# rs232_part.net
KiCad netlist of a schematic drawn in Altium Designer
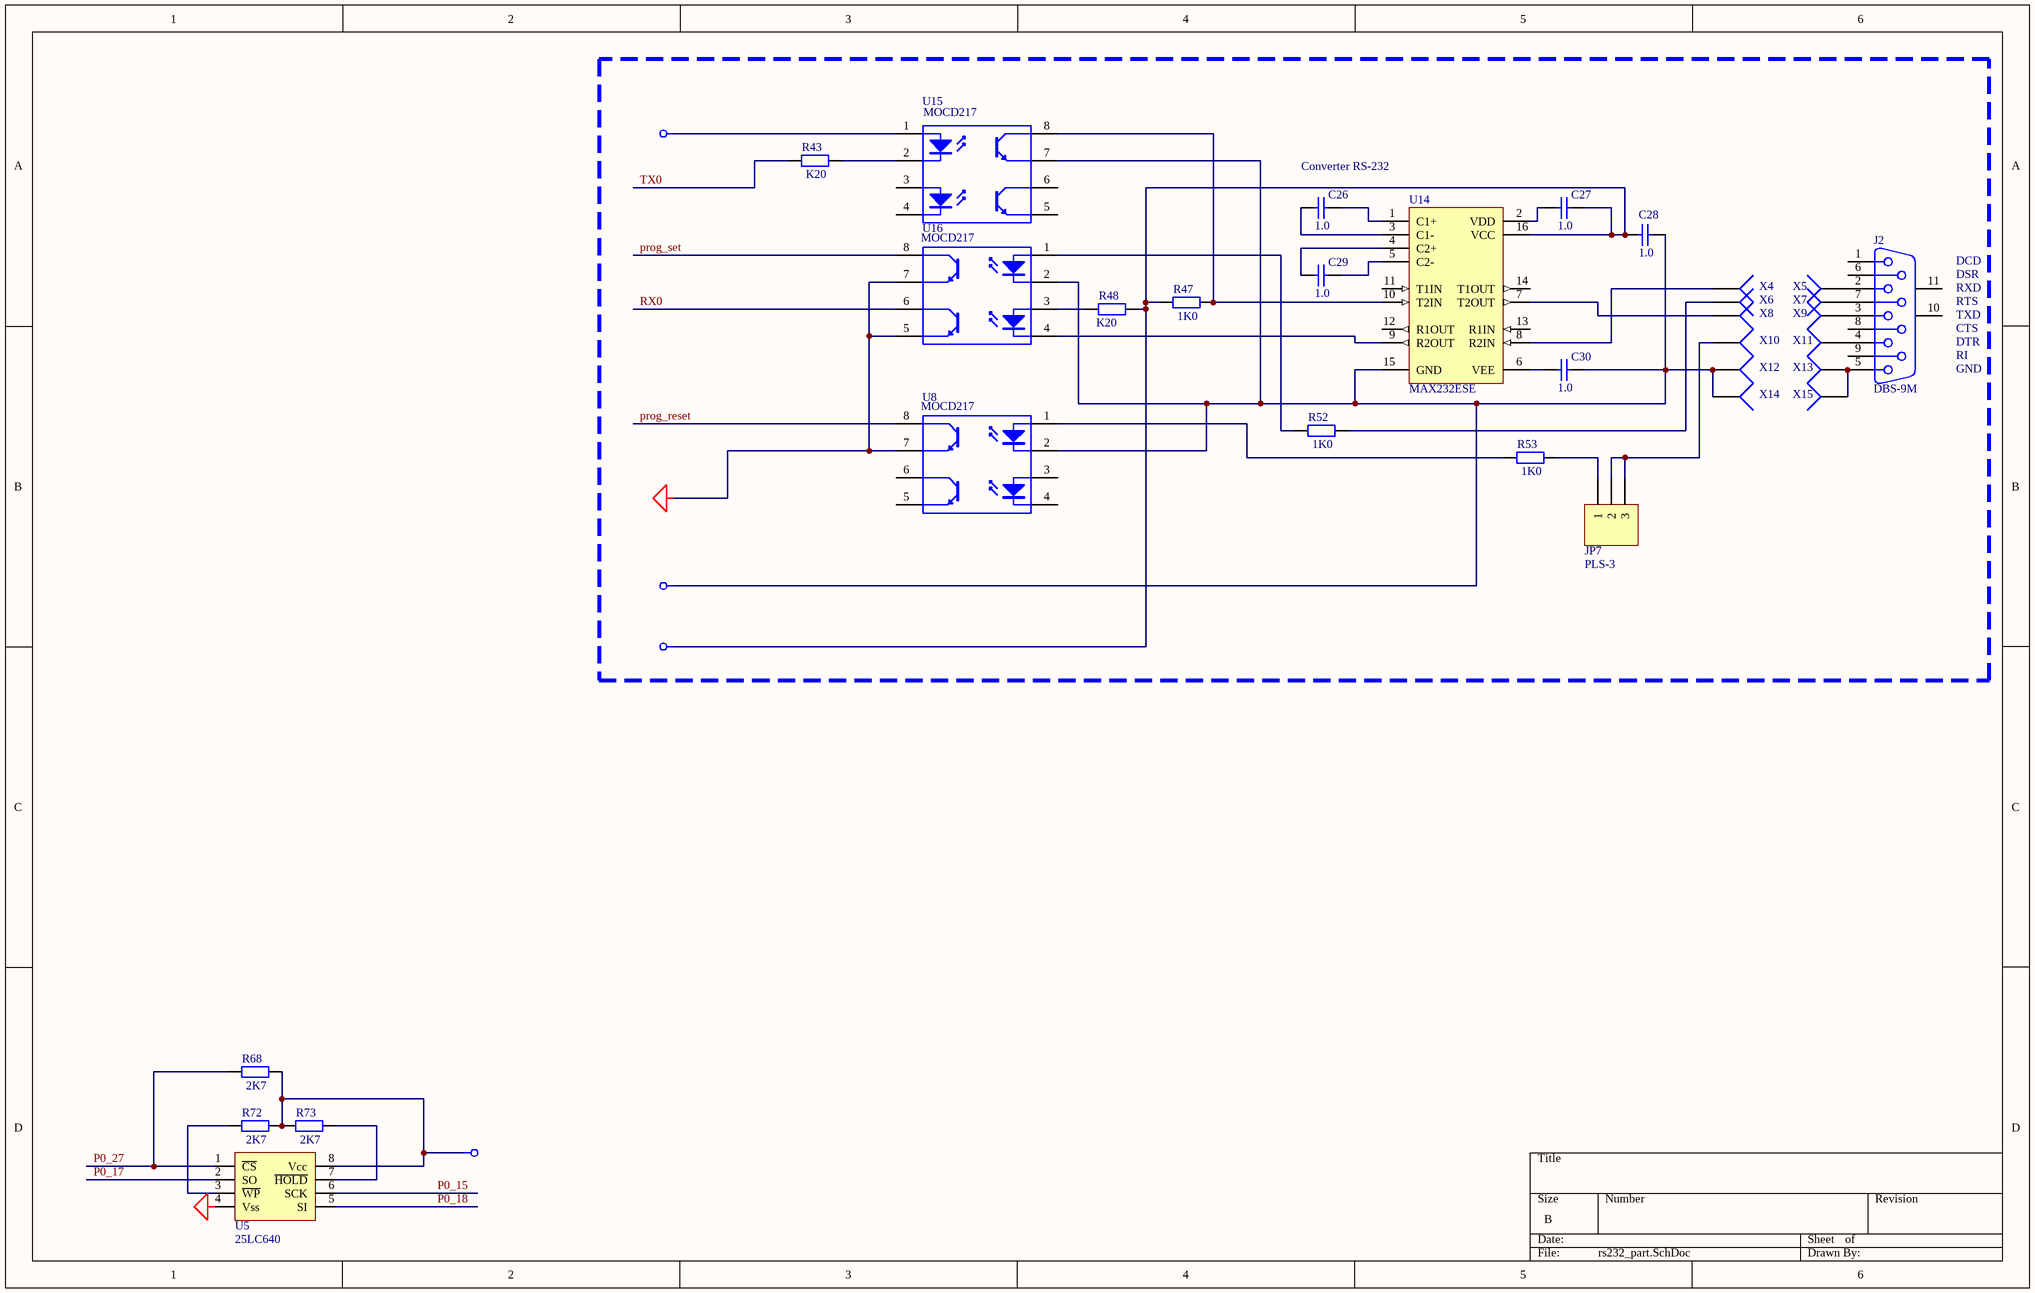
[diagram p0: rs232_part.SchDoc]

(export (version "E")
  (design (tool "Eeschema 10.0.6"))
  (components
    (comp (ref "C26")
      (value "1.0")
      (footprint "C3216-1206")
      (description "Capacitor (Semiconductor SIM Model)")
      (fields (field (name "MANUFACTURER") "Generic Components") (field (name "PUBLISHER") "Altium Limited"))
      (libsource (lib "Miscellaneous Devices") (part "Cap Semi"))
    )
    (comp (ref "C27")
      (value "1.0")
      (footprint "_1206")
      (description "Capacitor (Semiconductor SIM Model)")
      (fields (field (name "MANUFACTURER") "Generic Components") (field (name "PUBLISHER") "Altium Limited"))
      (libsource (lib "Miscellaneous Devices") (part "Cap Semi"))
    )
    (comp (ref "C28")
      (value "1.0")
      (footprint "C3216-1206")
      (description "Capacitor (Semiconductor SIM Model)")
      (fields (field (name "MANUFACTURER") "Generic Components") (field (name "PUBLISHER") "Altium Limited"))
      (libsource (lib "Miscellaneous Devices") (part "Cap Semi"))
    )
    (comp (ref "C29")
      (value "1.0")
      (footprint "C3216-1206")
      (description "Capacitor (Semiconductor SIM Model)")
      (fields (field (name "MANUFACTURER") "Generic Components") (field (name "PUBLISHER") "Altium Limited"))
      (libsource (lib "Miscellaneous Devices") (part "Cap Semi"))
    )
    (comp (ref "C30")
      (value "1.0")
      (footprint "C3216-1206")
      (description "Capacitor (Semiconductor SIM Model)")
      (fields (field (name "MANUFACTURER") "Generic Components") (field (name "PUBLISHER") "Altium Limited"))
      (libsource (lib "Miscellaneous Devices") (part "Cap Semi"))
    )
    (comp (ref "J2")
      (value "DBS-9M")
      (footprint "DSUB_N9")
      (description "Receptacle Assembly, 9 Position, Right Angle")
      (fields (field (name "MANUFACTURER") "Generic Components") (field (name "PUBLISHER") "Altium Limited"))
      (libsource (lib "Miscellaneous Connectors") (part "D Connector 9"))
    )
    (comp (ref "JP7")
      (value "PLS-3")
      (footprint "HDR1X3")
      (description "Header, 3-Pin")
      (fields (field (name "MANUFACTURER") "Generic Components") (field (name "PUBLISHER") "Altium Limited"))
      (libsource (lib "Miscellaneous Connectors") (part "Header 3"))
    )
    (comp (ref "R43")
      (value "K20")
      (footprint "_1206")
      (description "Resistor")
      (fields (field (name "MANUFACTURER") "Generic Components") (field (name "PUBLISHER") "Altium Limited"))
      (libsource (lib "Miscellaneous Devices") (part "Res2"))
    )
    (comp (ref "R47")
      (value "1K0")
      (footprint "_1206")
      (description "Resistor")
      (fields (field (name "MANUFACTURER") "Generic Components") (field (name "PUBLISHER") "Altium Limited"))
      (libsource (lib "Miscellaneous Devices") (part "Res2"))
    )
    (comp (ref "R48")
      (value "K20")
      (footprint "_1206")
      (description "Resistor")
      (fields (field (name "MANUFACTURER") "Generic Components") (field (name "PUBLISHER") "Altium Limited"))
      (libsource (lib "Miscellaneous Devices") (part "Res2"))
    )
    (comp (ref "R52")
      (value "1K0")
      (footprint "_1206")
      (description "Resistor")
      (fields (field (name "MANUFACTURER") "Generic Components") (field (name "PUBLISHER") "Altium Limited"))
      (libsource (lib "Miscellaneous Devices") (part "Res2"))
    )
    (comp (ref "R53")
      (value "1K0")
      (footprint "_1206")
      (description "Resistor")
      (fields (field (name "MANUFACTURER") "Generic Components") (field (name "PUBLISHER") "Altium Limited"))
      (libsource (lib "Miscellaneous Devices") (part "Res2"))
    )
    (comp (ref "R68")
      (value "2K7")
      (footprint "_1206")
      (description "Resistor")
      (fields (field (name "MANUFACTURER") "Generic Components") (field (name "PUBLISHER") "Altium Limited"))
      (libsource (lib "Miscellaneous Devices") (part "Res2"))
    )
    (comp (ref "R72")
      (value "2K7")
      (footprint "_1206")
      (description "Resistor")
      (fields (field (name "MANUFACTURER") "Generic Components") (field (name "PUBLISHER") "Altium Limited"))
      (libsource (lib "Miscellaneous Devices") (part "Res2"))
    )
    (comp (ref "R73")
      (value "2K7")
      (footprint "_1206")
      (description "Resistor")
      (fields (field (name "MANUFACTURER") "Generic Components") (field (name "PUBLISHER") "Altium Limited"))
      (libsource (lib "Miscellaneous Devices") (part "Res2"))
    )
    (comp (ref "U5") (value "25LC640") (footprint "SO-G8/D5") (libsource (lib "PAL") (part "25LC640")))
    (comp (ref "U8") (value "MOCD217") (footprint "SO-G8") (libsource (lib "PAL") (part "MOCD217")))
    (comp (ref "U14")
      (value "MAX232ESE")
      (footprint "SO-G16")
      (description "+5V Powered, Multi-Channel RS-232 Driver/Receiver")
      (fields (field (name "MANUFACTURER") "Maxim") (field (name "PUBLISHER") "Altium Limited"))
      (libsource (lib "Maxim Communication Transceiver") (part "MAX232ESE"))
    )
    (comp (ref "U15") (value "MOCD217") (footprint "SO-G8") (libsource (lib "PAL") (part "MOCD217")))
    (comp (ref "U16") (value "MOCD217") (footprint "SO-G8") (libsource (lib "PAL") (part "MOCD217")))
    (comp (ref "X4")
      (value "~")
      (footprint "PIN1")
      (description "Socket")
      (fields (field (name "MANUFACTURER") "Generic Components") (field (name "PUBLISHER") "Altium Limited"))
      (libsource (lib "Miscellaneous Connectors") (part "Socket"))
    )
    (comp (ref "X5")
      (value "~")
      (footprint "PIN1")
      (description "Socket")
      (fields (field (name "MANUFACTURER") "Generic Components") (field (name "PUBLISHER") "Altium Limited"))
      (libsource (lib "Miscellaneous Connectors") (part "Socket"))
    )
    (comp (ref "X6")
      (value "~")
      (footprint "PIN1")
      (description "Socket")
      (fields (field (name "MANUFACTURER") "Generic Components") (field (name "PUBLISHER") "Altium Limited"))
      (libsource (lib "Miscellaneous Connectors") (part "Socket"))
    )
    (comp (ref "X7")
      (value "~")
      (footprint "PIN1")
      (description "Socket")
      (fields (field (name "MANUFACTURER") "Generic Components") (field (name "PUBLISHER") "Altium Limited"))
      (libsource (lib "Miscellaneous Connectors") (part "Socket"))
    )
    (comp (ref "X8")
      (value "~")
      (footprint "PIN1")
      (description "Socket")
      (fields (field (name "MANUFACTURER") "Generic Components") (field (name "PUBLISHER") "Altium Limited"))
      (libsource (lib "Miscellaneous Connectors") (part "Socket"))
    )
    (comp (ref "X9")
      (value "~")
      (footprint "PIN1")
      (description "Socket")
      (fields (field (name "MANUFACTURER") "Generic Components") (field (name "PUBLISHER") "Altium Limited"))
      (libsource (lib "Miscellaneous Connectors") (part "Socket"))
    )
    (comp (ref "X10")
      (value "~")
      (footprint "PIN1")
      (description "Socket")
      (fields (field (name "MANUFACTURER") "Generic Components") (field (name "PUBLISHER") "Altium Limited"))
      (libsource (lib "Miscellaneous Connectors") (part "Socket"))
    )
    (comp (ref "X11")
      (value "~")
      (footprint "PIN1")
      (description "Socket")
      (fields (field (name "MANUFACTURER") "Generic Components") (field (name "PUBLISHER") "Altium Limited"))
      (libsource (lib "Miscellaneous Connectors") (part "Socket"))
    )
    (comp (ref "X12")
      (value "~")
      (footprint "PIN1")
      (description "Socket")
      (fields (field (name "MANUFACTURER") "Generic Components") (field (name "PUBLISHER") "Altium Limited"))
      (libsource (lib "Miscellaneous Connectors") (part "Socket"))
    )
    (comp (ref "X13")
      (value "~")
      (footprint "PIN1")
      (description "Socket")
      (fields (field (name "MANUFACTURER") "Generic Components") (field (name "PUBLISHER") "Altium Limited"))
      (libsource (lib "Miscellaneous Connectors") (part "Socket"))
    )
    (comp (ref "X14")
      (value "~")
      (footprint "PIN1")
      (description "Socket")
      (fields (field (name "MANUFACTURER") "Generic Components") (field (name "PUBLISHER") "Altium Limited"))
      (libsource (lib "Miscellaneous Connectors") (part "Socket"))
    )
    (comp (ref "X15")
      (value "~")
      (footprint "PIN1")
      (description "Socket")
      (fields (field (name "MANUFACTURER") "Generic Components") (field (name "PUBLISHER") "Altium Limited"))
      (libsource (lib "Miscellaneous Connectors") (part "Socket"))
    )
  )
  (nets
    (net (code "1") (name "+3v3") (class "Default")
      (node (ref "U15") (pin "1") (pinfunction "A_1") (pintype "passive"))
    )
    (net (code "2") (name "+5v") (class "Default")
      (node (ref "R68") (pin "2") (pinfunction "2_2") (pintype "passive"))
      (node (ref "R72") (pin "2") (pinfunction "2_2") (pintype "passive"))
      (node (ref "R73") (pin "1") (pinfunction "1_1") (pintype "passive"))
      (node (ref "U5") (pin "8") (pinfunction "Vcc_8") (pintype "passive"))
    )
    (net (code "3") (name "+5v_iz") (class "Default")
      (node (ref "C27") (pin "2") (pinfunction "2_2") (pintype "passive"))
      (node (ref "C28") (pin "1") (pinfunction "1_1") (pintype "passive"))
      (node (ref "R47") (pin "1") (pinfunction "1_1") (pintype "passive"))
      (node (ref "R48") (pin "2") (pinfunction "2_2") (pintype "passive"))
      (node (ref "U14") (pin "16") (pinfunction "VCC_16") (pintype "power_in"))
    )
    (net (code "4") (name "-5v_iz") (class "Default")
      (node (ref "C28") (pin "2") (pinfunction "2_2") (pintype "passive"))
      (node (ref "C30") (pin "2") (pinfunction "2_2") (pintype "passive"))
      (node (ref "U14") (pin "15") (pinfunction "GND_15") (pintype "power_in"))
      (node (ref "U15") (pin "7") (pinfunction "E_7") (pintype "passive"))
      (node (ref "U16") (pin "2") (pinfunction "K_2") (pintype "passive"))
      (node (ref "U8") (pin "2") (pinfunction "K_2") (pintype "passive"))
      (node (ref "X12") (pin "1") (pinfunction "1_1") (pintype "passive"))
      (node (ref "X14") (pin "1") (pinfunction "1_1") (pintype "passive"))
    )
    (net (code "5") (name "/P0_15") (class "Default")
      (node (ref "U5") (pin "6") (pinfunction "SCK_6") (pintype "passive"))
    )
    (net (code "6") (name "/P0_17") (class "Default")
      (node (ref "U5") (pin "2") (pinfunction "SO_2") (pintype "passive"))
    )
    (net (code "7") (name "/P0_18") (class "Default")
      (node (ref "U5") (pin "5") (pinfunction "SI_5") (pintype "passive"))
    )
    (net (code "8") (name "/P0_27") (class "Default")
      (node (ref "R68") (pin "1") (pinfunction "1_1") (pintype "passive"))
      (node (ref "U5") (pin "1") (pinfunction "~{CS}_1") (pintype "passive"))
    )
    (net (code "9") (name "/RX0") (class "Default")
      (node (ref "U16") (pin "6") (pinfunction "C_6") (pintype "passive"))
    )
    (net (code "10") (name "/TX0") (class "Default")
      (node (ref "R43") (pin "1") (pinfunction "1_1") (pintype "passive"))
    )
    (net (code "11") (name "/prog_reset") (class "Default")
      (node (ref "U8") (pin "8") (pinfunction "C_8") (pintype "passive"))
    )
    (net (code "12") (name "/prog_set") (class "Default")
      (node (ref "U16") (pin "8") (pinfunction "C_8") (pintype "passive"))
    )
    (net (code "13") (name "GND") (class "Default")
      (node (ref "U16") (pin "5") (pinfunction "E_5") (pintype "passive"))
      (node (ref "U16") (pin "7") (pinfunction "E_7") (pintype "passive"))
      (node (ref "U5") (pin "4") (pinfunction "Vss_4") (pintype "passive"))
      (node (ref "U8") (pin "7") (pinfunction "E_7") (pintype "passive"))
    )
    (net (code "14") (name "Net-(J2-Pad2)") (class "Default")
      (node (ref "J2") (pin "2") (pinfunction "2_2") (pintype "passive"))
      (node (ref "X5") (pin "1") (pinfunction "1_1") (pintype "passive"))
    )
    (net (code "15") (name "Net-(J2-Pad3)") (class "Default")
      (node (ref "J2") (pin "3") (pinfunction "3_3") (pintype "passive"))
      (node (ref "X9") (pin "1") (pinfunction "1_1") (pintype "passive"))
    )
    (net (code "16") (name "Net-(J2-Pad4)") (class "Default")
      (node (ref "J2") (pin "4") (pinfunction "4_4") (pintype "passive"))
      (node (ref "X11") (pin "1") (pinfunction "1_1") (pintype "passive"))
    )
    (net (code "17") (name "Net-(J2-Pad5)") (class "Default")
      (node (ref "J2") (pin "5") (pinfunction "5_5") (pintype "passive"))
      (node (ref "X13") (pin "1") (pinfunction "1_1") (pintype "passive"))
      (node (ref "X15") (pin "1") (pinfunction "1_1") (pintype "passive"))
    )
    (net (code "18") (name "Net-(J2-Pad7)") (class "Default")
      (node (ref "J2") (pin "7") (pinfunction "7_7") (pintype "passive"))
      (node (ref "X7") (pin "1") (pinfunction "1_1") (pintype "passive"))
    )
    (net (code "19") (name "Net-(JP7-Pad1)") (class "Default")
      (node (ref "JP7") (pin "1") (pinfunction "1_1") (pintype "passive"))
      (node (ref "R53") (pin "2") (pinfunction "2_2") (pintype "passive"))
    )
    (net (code "20") (name "Net-(JP7-Pad2)") (class "Default")
      (node (ref "JP7") (pin "2") (pinfunction "2_2") (pintype "passive"))
      (node (ref "JP7") (pin "3") (pinfunction "3_3") (pintype "passive"))
      (node (ref "X10") (pin "1") (pinfunction "1_1") (pintype "passive"))
    )
    (net (code "21") (name "Net-(R43-Pad2)") (class "Default")
      (node (ref "R43") (pin "2") (pinfunction "2_2") (pintype "passive"))
      (node (ref "U15") (pin "2") (pinfunction "K_2") (pintype "passive"))
    )
    (net (code "22") (name "Net-(R48-Pad1)") (class "Default")
      (node (ref "R48") (pin "1") (pinfunction "1_1") (pintype "passive"))
      (node (ref "U16") (pin "3") (pinfunction "A_3") (pintype "passive"))
    )
    (net (code "23") (name "Net-(R52-Pad1)") (class "Default")
      (node (ref "R52") (pin "1") (pinfunction "1_1") (pintype "passive"))
      (node (ref "U16") (pin "1") (pinfunction "A_1") (pintype "passive"))
    )
    (net (code "24") (name "Net-(R52-Pad2)") (class "Default")
      (node (ref "R52") (pin "2") (pinfunction "2_2") (pintype "passive"))
      (node (ref "X6") (pin "1") (pinfunction "1_1") (pintype "passive"))
    )
    (net (code "25") (name "Net-(R53-Pad1)") (class "Default")
      (node (ref "R53") (pin "1") (pinfunction "1_1") (pintype "passive"))
      (node (ref "U8") (pin "1") (pinfunction "A_1") (pintype "passive"))
    )
    (net (code "26") (name "Net-(U5-~{HOLD})") (class "Default")
      (node (ref "R73") (pin "2") (pinfunction "2_2") (pintype "passive"))
      (node (ref "U5") (pin "7") (pinfunction "~{HOLD}_7") (pintype "passive"))
    )
    (net (code "27") (name "Net-(U5-~{WP})") (class "Default")
      (node (ref "R72") (pin "1") (pinfunction "1_1") (pintype "passive"))
      (node (ref "U5") (pin "3") (pinfunction "~{WP}_3") (pintype "passive"))
    )
    (net (code "28") (name "Net-(U14-C1+)") (class "Default")
      (node (ref "C26") (pin "2") (pinfunction "2_2") (pintype "passive"))
      (node (ref "U14") (pin "1") (pinfunction "C1+_1") (pintype "passive"))
    )
    (net (code "29") (name "Net-(U14-C1-)") (class "Default")
      (node (ref "C26") (pin "1") (pinfunction "1_1") (pintype "passive"))
      (node (ref "U14") (pin "3") (pinfunction "C1-_3") (pintype "passive"))
    )
    (net (code "30") (name "Net-(U14-C2+)") (class "Default")
      (node (ref "C29") (pin "1") (pinfunction "1_1") (pintype "passive"))
      (node (ref "U14") (pin "4") (pinfunction "C2+_4") (pintype "passive"))
    )
    (net (code "31") (name "Net-(U14-C2-)") (class "Default")
      (node (ref "C29") (pin "2") (pinfunction "2_2") (pintype "passive"))
      (node (ref "U14") (pin "5") (pinfunction "C2-_5") (pintype "passive"))
    )
    (net (code "32") (name "Net-(U14-R2IN)") (class "Default")
      (node (ref "U14") (pin "8") (pinfunction "R2IN_8") (pintype "input"))
      (node (ref "X4") (pin "1") (pinfunction "1_1") (pintype "passive"))
    )
    (net (code "33") (name "Net-(U14-R2OUT)") (class "Default")
      (node (ref "U14") (pin "9") (pinfunction "R2OUT_9") (pintype "output"))
      (node (ref "U16") (pin "4") (pinfunction "K_4") (pintype "passive"))
    )
    (net (code "34") (name "Net-(U14-T2IN)") (class "Default")
      (node (ref "R47") (pin "2") (pinfunction "2_2") (pintype "passive"))
      (node (ref "U14") (pin "10") (pinfunction "T2IN_10") (pintype "input"))
      (node (ref "U15") (pin "8") (pinfunction "C_8") (pintype "passive"))
    )
    (net (code "35") (name "Net-(U14-T2OUT)") (class "Default")
      (node (ref "U14") (pin "7") (pinfunction "T2OUT_7") (pintype "output"))
      (node (ref "X8") (pin "1") (pinfunction "1_1") (pintype "passive"))
    )
    (net (code "36") (name "Net-(U14-VDD)") (class "Default")
      (node (ref "C27") (pin "1") (pinfunction "1_1") (pintype "passive"))
      (node (ref "U14") (pin "2") (pinfunction "VDD_2") (pintype "power_in"))
    )
    (net (code "37") (name "Net-(U14-VEE)") (class "Default")
      (node (ref "C30") (pin "1") (pinfunction "1_1") (pintype "passive"))
      (node (ref "U14") (pin "6") (pinfunction "VEE_6") (pintype "power_in"))
    )
    (net (code "38") (name "unconnected-(J2-MH1-Pad10)") (class "Default")
      (node (ref "J2") (pin "10") (pinfunction "MH1_10") (pintype "passive"))
    )
    (net (code "39") (name "unconnected-(J2-MH2-Pad11)") (class "Default")
      (node (ref "J2") (pin "11") (pinfunction "MH2_11") (pintype "passive"))
    )
    (net (code "40") (name "unconnected-(J2-Pad1)") (class "Default")
      (node (ref "J2") (pin "1") (pinfunction "1_1") (pintype "passive"))
    )
    (net (code "41") (name "unconnected-(J2-Pad6)") (class "Default")
      (node (ref "J2") (pin "6") (pinfunction "6_6") (pintype "passive"))
    )
    (net (code "42") (name "unconnected-(J2-Pad8)") (class "Default")
      (node (ref "J2") (pin "8") (pinfunction "8_8") (pintype "passive"))
    )
    (net (code "43") (name "unconnected-(J2-Pad9)") (class "Default")
      (node (ref "J2") (pin "9") (pinfunction "9_9") (pintype "passive"))
    )
    (net (code "44") (name "unconnected-(U8-A-Pad3)") (class "Default")
      (node (ref "U8") (pin "3") (pinfunction "A_3") (pintype "passive"))
    )
    (net (code "45") (name "unconnected-(U8-C-Pad6)") (class "Default")
      (node (ref "U8") (pin "6") (pinfunction "C_6") (pintype "passive"))
    )
    (net (code "46") (name "unconnected-(U8-E-Pad5)") (class "Default")
      (node (ref "U8") (pin "5") (pinfunction "E_5") (pintype "passive"))
    )
    (net (code "47") (name "unconnected-(U8-K-Pad4)") (class "Default")
      (node (ref "U8") (pin "4") (pinfunction "K_4") (pintype "passive"))
    )
    (net (code "48") (name "unconnected-(U14-R1IN-Pad13)") (class "Default")
      (node (ref "U14") (pin "13") (pinfunction "R1IN_13") (pintype "input"))
    )
    (net (code "49") (name "unconnected-(U14-R1OUT-Pad12)") (class "Default")
      (node (ref "U14") (pin "12") (pinfunction "R1OUT_12") (pintype "output"))
    )
    (net (code "50") (name "unconnected-(U14-T1IN-Pad11)") (class "Default")
      (node (ref "U14") (pin "11") (pinfunction "T1IN_11") (pintype "input"))
    )
    (net (code "51") (name "unconnected-(U14-T1OUT-Pad14)") (class "Default")
      (node (ref "U14") (pin "14") (pinfunction "T1OUT_14") (pintype "output"))
    )
    (net (code "52") (name "unconnected-(U15-A-Pad3)") (class "Default")
      (node (ref "U15") (pin "3") (pinfunction "A_3") (pintype "passive"))
    )
    (net (code "53") (name "unconnected-(U15-C-Pad6)") (class "Default")
      (node (ref "U15") (pin "6") (pinfunction "C_6") (pintype "passive"))
    )
    (net (code "54") (name "unconnected-(U15-E-Pad5)") (class "Default")
      (node (ref "U15") (pin "5") (pinfunction "E_5") (pintype "passive"))
    )
    (net (code "55") (name "unconnected-(U15-K-Pad4)") (class "Default")
      (node (ref "U15") (pin "4") (pinfunction "K_4") (pintype "passive"))
    )
  )
)
